# Master.net
KiCad netlist of a schematic drawn in Altium Designer
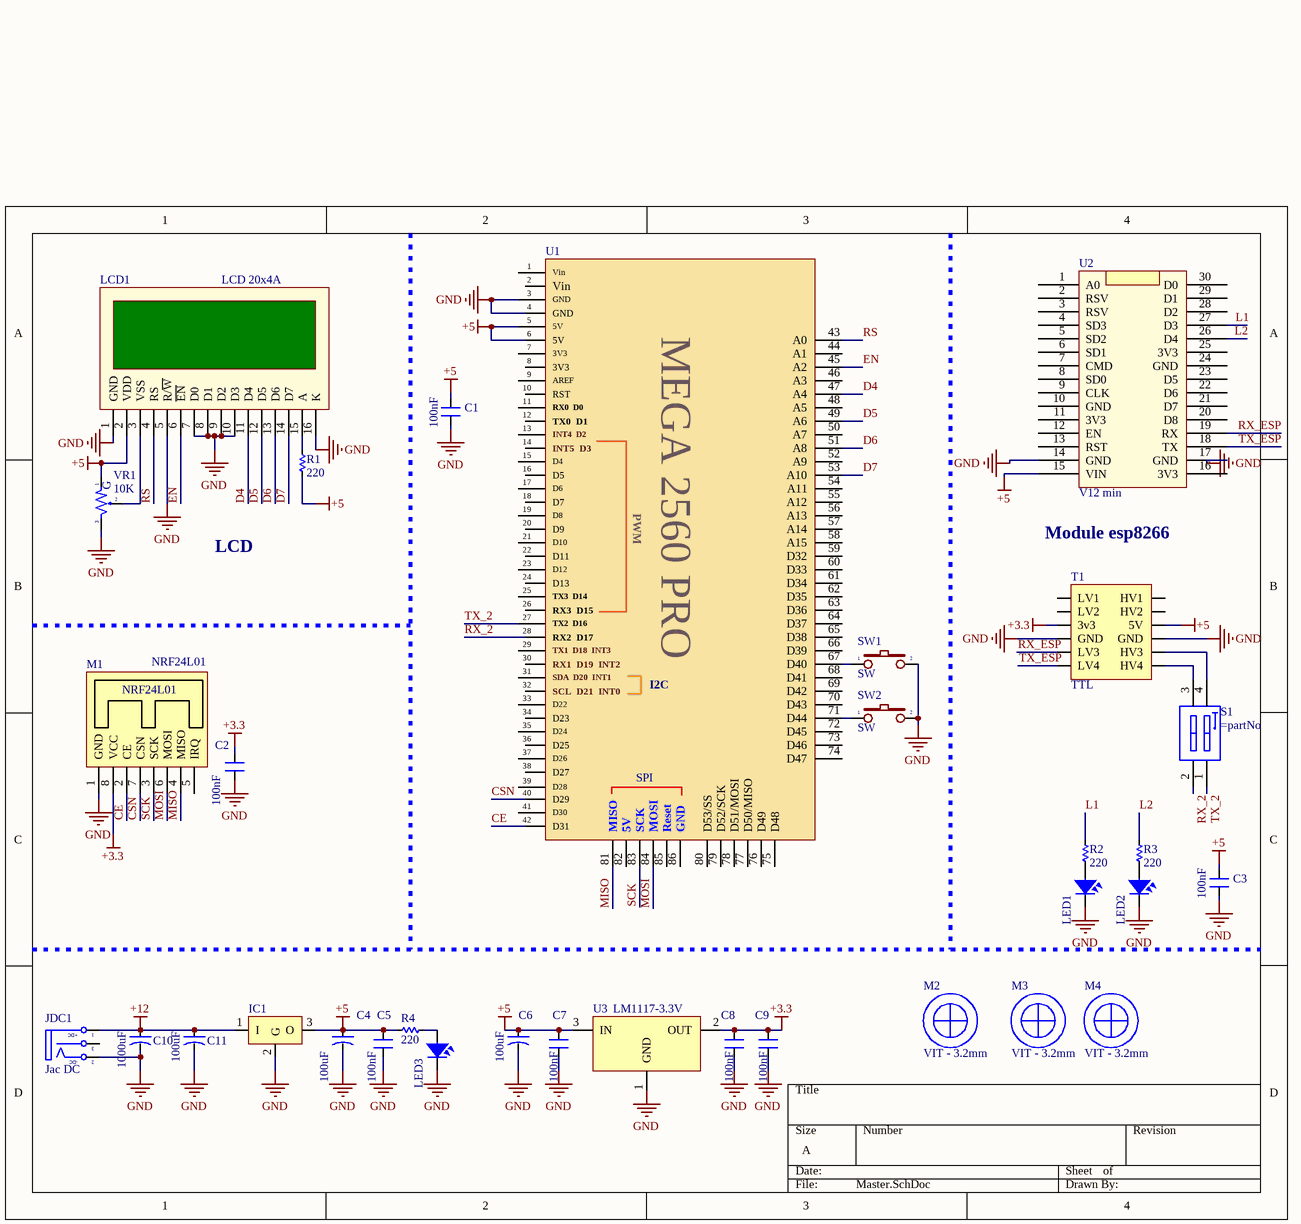
[diagram p0: Master.SchDoc]

(export (version "E")
  (design (tool "Eeschema 10.0.6"))
  (components
    (comp (ref "C1") (value "100nF") (footprint "CN1.5") (libsource (lib "thu vien 3d") (part "CN")))
    (comp (ref "C2") (value "100nF") (footprint "CN1.5") (libsource (lib "thu vien 3d") (part "CN")))
    (comp (ref "C3") (value "100nF") (footprint "CN1.5") (libsource (lib "thu vien 3d") (part "CN")))
    (comp (ref "C4")
      (value "100uF")
      (footprint "CA-ALU-5")
      (description "Capacitor (Semiconductor SIM Model)")
      (fields (field (name "PUBLISHER") "Altium Limited"))
      (libsource (lib "thu vien 3d") (part "CN-ALU-DIP"))
    )
    (comp (ref "C5") (value "100nF") (footprint "CN1.5") (libsource (lib "thu vien 3d") (part "CN")))
    (comp (ref "C6")
      (value "100uF")
      (footprint "CA-ALU-5")
      (description "Capacitor (Semiconductor SIM Model)")
      (fields (field (name "PUBLISHER") "Altium Limited"))
      (libsource (lib "thu vien 3d") (part "CN-ALU-DIP"))
    )
    (comp (ref "C7") (value "100nF") (footprint "CN1.5") (libsource (lib "thu vien 3d") (part "CN")))
    (comp (ref "C8") (value "100nF") (footprint "CN1.5") (libsource (lib "thu vien 3d") (part "CN")))
    (comp (ref "C9") (value "100nF") (footprint "CN1.5") (libsource (lib "thu vien 3d") (part "CN")))
    (comp (ref "C10")
      (value "1000uF")
      (footprint "CA-ALU-6.3")
      (description "Capacitor (Semiconductor SIM Model)")
      (fields (field (name "PUBLISHER") "Altium Limited"))
      (libsource (lib "thu vien 3d") (part "CN-ALU-DIP"))
    )
    (comp (ref "C11")
      (value "100uF")
      (footprint "CA-ALU-5")
      (description "Capacitor (Semiconductor SIM Model)")
      (fields (field (name "PUBLISHER") "Altium Limited"))
      (libsource (lib "thu vien 3d") (part "CN-ALU-DIP"))
    )
    (comp (ref "IC1")
      (value "LM78xx")
      (footprint "TO220-123")
      (description "Positive Voltage Regulator")
      (fields (field (name "PUBLISHER") "Altium Limited"))
      (libsource (lib "thu vien 3d") (part "LM78xx"))
    )
    (comp (ref "JDC1")
      (value "Jac DC")
      (footprint "DC0")
      (description "Jac DC input")
      (libsource (lib "thu vien 3d") (part "DCIN"))
    )
    (comp (ref "LCD1")
      (value "LCD 20x4A")
      (footprint "LCD20X4A")
      (description "LCD dipslay 20 char, 4 line")
      (libsource (lib "thu vien 3d") (part "LCD20x4A"))
    )
    (comp (ref "LED1")
      (value "LED")
      (footprint "LED-3MM-RED")
      (description "LED Single colour Green and Red")
      (libsource (lib "thu vien 3d") (part "LED"))
    )
    (comp (ref "LED2")
      (value "LED")
      (footprint "LED-3MM-RED")
      (description "LED Single colour Green and Red")
      (libsource (lib "thu vien 3d") (part "LED"))
    )
    (comp (ref "LED3")
      (value "LED")
      (footprint "LED-3MM-RED")
      (description "LED Single colour Green and Red")
      (libsource (lib "thu vien 3d") (part "LED"))
    )
    (comp (ref "M1")
      (value "NRF24L01")
      (footprint "NRF24L01")
      (libsource (lib "thu vien 3d") (part "NRF24L01"))
    )
    (comp (ref "M2")
      (value "VIT - 3.2mm")
      (footprint "VIT - 3.2MM_2")
      (libsource (lib "Nichietsuvn") (part "VIT - 3.2mm"))
    )
    (comp (ref "M3")
      (value "VIT - 3.2mm")
      (footprint "VIT - 3.2MM_2")
      (libsource (lib "Nichietsuvn") (part "VIT - 3.2mm"))
    )
    (comp (ref "M4")
      (value "VIT - 3.2mm")
      (footprint "VIT - 3.2MM_2")
      (libsource (lib "Nichietsuvn") (part "VIT - 3.2mm"))
    )
    (comp (ref "R1")
      (value "220")
      (footprint "RES-1/4W-SMALL")
      (description "Res")
      (fields
        (field (name "MANUFACTURER") "Generic Components")
        (field (name "PUBLISHER") "Altium Hobart Technology Centre")
      )
      (libsource (lib "thu vien 3d") (part "Res"))
    )
    (comp (ref "R2")
      (value "220")
      (footprint "RES-1/4WD")
      (description "Res")
      (fields
        (field (name "MANUFACTURER") "Generic Components")
        (field (name "PUBLISHER") "Altium Hobart Technology Centre")
      )
      (libsource (lib "thu vien 3d") (part "Res"))
    )
    (comp (ref "R3")
      (value "220")
      (footprint "RES-1/4WD")
      (description "Res")
      (fields
        (field (name "MANUFACTURER") "Generic Components")
        (field (name "PUBLISHER") "Altium Hobart Technology Centre")
      )
      (libsource (lib "thu vien 3d") (part "Res"))
    )
    (comp (ref "R4")
      (value "220")
      (footprint "RES-1/4W")
      (description "Res")
      (fields
        (field (name "MANUFACTURER") "Generic Components")
        (field (name "PUBLISHER") "Altium Hobart Technology Centre")
      )
      (libsource (lib "thu vien 3d") (part "Res"))
    )
    (comp (ref "S1")
      (value "~")
      (footprint "SW-DIP2")
      (description "WS-DITV 2.54 mm small compact THT flat actuator with top tape")
      (fields
        (field (name "MANUFACTURER") "Wurth Elektronik")
        (field (name "PART NO.") "418127160902")
        (field (name "CREATED BY") "Baojun Chen")
      )
      (libsource (lib "thu vien 3d") (part "SWDIP2"))
    )
    (comp (ref "SW1")
      (value "SW")
      (footprint "SW1-DIP")
      (description "Switch button 2 pin")
      (libsource (lib "thu vien 3d") (part "SW2"))
    )
    (comp (ref "SW2")
      (value "SW")
      (footprint "SW1-DIP")
      (description "Switch button 2 pin")
      (libsource (lib "thu vien 3d") (part "SW2"))
    )
    (comp (ref "T1")
      (value "TTL")
      (footprint "TTL")
      (description "WR-PHD 2.54 mm Dual Socket Header")
      (fields
        (field (name "MANUFACTURER") "Würth Elektronik eiSos GmbH")
        (field (name "PARTNO") "61301221821")
        (field (name "CREATED BY") "Karrer Zheng")
      )
      (libsource (lib "Nichietsuvn") (part "TTL"))
    )
    (comp (ref "U1")
      (value "Le Quoc Huy")
      (footprint "Arduino Mega Pro Mini")
      (libsource (lib "LIB_HUY_isolator") (part "Arduino mega 2560 Pro"))
    )
    (comp (ref "U2")
      (value "V12 min")
      (footprint "Module ESP 8266_min")
      (libsource (lib "Nichietsuvn") (part "Module ESP8266"))
    )
    (comp (ref "U3")
      (value "LM1117-3.3V")
      (footprint "SOT223")
      (description "800mA Low-Dropout Linear Regulator")
      (fields (field (name "CREATOR") "Nguyen Ba Bien"))
      (libsource (lib "thu vien 3d") (part "LM1117"))
    )
    (comp (ref "VR1")
      (value "10K")
      (footprint "VR-S3")
      (description "Var Resistor")
      (libsource (lib "thu vien 3d") (part "VR-S"))
    )
  )
  (nets
    (net (code "1") (name "+3.3") (class "Default")
      (node (ref "C2") (pin "2") (pinfunction "2_2") (pintype "passive"))
      (node (ref "C8") (pin "2") (pinfunction "2_2") (pintype "passive"))
      (node (ref "C9") (pin "2") (pinfunction "2_2") (pintype "passive"))
      (node (ref "M1") (pin "8") (pinfunction "VCC_8") (pintype "passive"))
      (node (ref "T1") (pin "3") (pinfunction "3v3_3") (pintype "passive"))
      (node (ref "U3") (pin "2") (pinfunction "OUT_2") (pintype "passive"))
    )
    (net (code "2") (name "+5") (class "Default")
      (node (ref "C1") (pin "2") (pinfunction "2_2") (pintype "passive"))
      (node (ref "C3") (pin "2") (pinfunction "2_2") (pintype "passive"))
      (node (ref "C4") (pin "1") (pinfunction "1_1") (pintype "passive"))
      (node (ref "C5") (pin "2") (pinfunction "2_2") (pintype "passive"))
      (node (ref "C6") (pin "1") (pinfunction "1_1") (pintype "passive"))
      (node (ref "C7") (pin "2") (pinfunction "2_2") (pintype "passive"))
      (node (ref "IC1") (pin "3") (pinfunction "O_3") (pintype "power_in"))
      (node (ref "LCD1") (pin "2") (pinfunction "VDD_2") (pintype "passive"))
      (node (ref "R1") (pin "2") (pinfunction "2_2") (pintype "passive"))
      (node (ref "R4") (pin "2") (pinfunction "2_2") (pintype "passive"))
      (node (ref "T1") (pin "10") (pinfunction "5V_10") (pintype "passive"))
      (node (ref "U1") (pin "5") (pinfunction "5V_5") (pintype "passive"))
      (node (ref "U1") (pin "6") (pinfunction "5V_6") (pintype "passive"))
      (node (ref "U2") (pin "15") (pinfunction "VIN_15") (pintype "passive"))
      (node (ref "U3") (pin "3") (pinfunction "IN_3") (pintype "passive"))
      (node (ref "VR1") (pin "1") (pinfunction "1_1") (pintype "passive"))
    )
    (net (code "3") (name "+12") (class "Default")
      (node (ref "C10") (pin "1") (pinfunction "1_1") (pintype "passive"))
      (node (ref "C11") (pin "1") (pinfunction "1_1") (pintype "passive"))
      (node (ref "IC1") (pin "1") (pinfunction "I_1") (pintype "power_in"))
      (node (ref "JDC1") (pin "1") (pinfunction "T_1") (pintype "passive"))
    )
    (net (code "4") (name "/CE") (class "Default")
      (node (ref "M1") (pin "2") (pinfunction "CE_2") (pintype "passive"))
      (node (ref "U1") (pin "42") (pinfunction "D31_42") (pintype "passive"))
    )
    (net (code "5") (name "/CSN") (class "Default")
      (node (ref "M1") (pin "7") (pinfunction "CSN_7") (pintype "passive"))
      (node (ref "U1") (pin "40") (pinfunction "D29_40") (pintype "passive"))
    )
    (net (code "6") (name "/D4") (class "Default")
      (node (ref "LCD1") (pin "11") (pinfunction "D4_11") (pintype "passive"))
      (node (ref "U1") (pin "47") (pinfunction "A4_47") (pintype "passive"))
    )
    (net (code "7") (name "/D5") (class "Default")
      (node (ref "LCD1") (pin "12") (pinfunction "D5_12") (pintype "passive"))
      (node (ref "U1") (pin "49") (pinfunction "A6_49") (pintype "passive"))
    )
    (net (code "8") (name "/D6") (class "Default")
      (node (ref "LCD1") (pin "13") (pinfunction "D6_13") (pintype "passive"))
      (node (ref "U1") (pin "51") (pinfunction "A8_51") (pintype "passive"))
    )
    (net (code "9") (name "/D7") (class "Default")
      (node (ref "LCD1") (pin "14") (pinfunction "D7_14") (pintype "passive"))
      (node (ref "U1") (pin "53") (pinfunction "A10_53") (pintype "passive"))
    )
    (net (code "10") (name "/EN") (class "Default")
      (node (ref "LCD1") (pin "6") (pinfunction "~{EN}_6") (pintype "passive"))
      (node (ref "U1") (pin "45") (pinfunction "A2_45") (pintype "passive"))
    )
    (net (code "11") (name "/L1") (class "Default")
      (node (ref "R2") (pin "2") (pinfunction "2_2") (pintype "passive"))
      (node (ref "U2") (pin "27") (pinfunction "D3_27") (pintype "passive"))
    )
    (net (code "12") (name "/L2") (class "Default")
      (node (ref "R3") (pin "2") (pinfunction "2_2") (pintype "passive"))
      (node (ref "U2") (pin "26") (pinfunction "D4_26") (pintype "passive"))
    )
    (net (code "13") (name "/MISO") (class "Default")
      (node (ref "M1") (pin "4") (pinfunction "MISO_4") (pintype "passive"))
      (node (ref "U1") (pin "81") (pinfunction "MISO_81") (pintype "passive"))
    )
    (net (code "14") (name "/MOSI") (class "Default")
      (node (ref "M1") (pin "6") (pinfunction "MOSI_6") (pintype "passive"))
      (node (ref "U1") (pin "84") (pinfunction "MOSI_84") (pintype "passive"))
    )
    (net (code "15") (name "/RS") (class "Default")
      (node (ref "LCD1") (pin "4") (pinfunction "RS_4") (pintype "passive"))
      (node (ref "U1") (pin "43") (pinfunction "A0_43") (pintype "passive"))
    )
    (net (code "16") (name "/RX_2") (class "Default")
      (node (ref "S1") (pin "2") (pinfunction "2_2") (pintype "passive"))
      (node (ref "U1") (pin "28") (pinfunction "RX2__D17_28") (pintype "passive"))
    )
    (net (code "17") (name "/RX_ESP") (class "Default")
      (node (ref "T1") (pin "5") (pinfunction "LV3_5") (pintype "passive"))
      (node (ref "U2") (pin "19") (pinfunction "RX_19") (pintype "passive"))
    )
    (net (code "18") (name "/SCK") (class "Default")
      (node (ref "M1") (pin "3") (pinfunction "SCK_3") (pintype "passive"))
      (node (ref "U1") (pin "83") (pinfunction "SCK_83") (pintype "passive"))
    )
    (net (code "19") (name "/TX_2") (class "Default")
      (node (ref "S1") (pin "1") (pinfunction "1_1") (pintype "passive"))
      (node (ref "U1") (pin "27") (pinfunction "TX2__D16_27") (pintype "passive"))
    )
    (net (code "20") (name "/TX_ESP") (class "Default")
      (node (ref "T1") (pin "6") (pinfunction "LV4_6") (pintype "passive"))
      (node (ref "U2") (pin "18") (pinfunction "TX_18") (pintype "passive"))
    )
    (net (code "21") (name "GND") (class "Default")
      (node (ref "C1") (pin "1") (pinfunction "1_1") (pintype "passive"))
      (node (ref "C10") (pin "2") (pinfunction "2_2") (pintype "passive"))
      (node (ref "C11") (pin "2") (pinfunction "2_2") (pintype "passive"))
      (node (ref "C2") (pin "1") (pinfunction "1_1") (pintype "passive"))
      (node (ref "C3") (pin "1") (pinfunction "1_1") (pintype "passive"))
      (node (ref "C4") (pin "2") (pinfunction "2_2") (pintype "passive"))
      (node (ref "C5") (pin "1") (pinfunction "1_1") (pintype "passive"))
      (node (ref "C6") (pin "2") (pinfunction "2_2") (pintype "passive"))
      (node (ref "C7") (pin "1") (pinfunction "1_1") (pintype "passive"))
      (node (ref "C8") (pin "1") (pinfunction "1_1") (pintype "passive"))
      (node (ref "C9") (pin "1") (pinfunction "1_1") (pintype "passive"))
      (node (ref "IC1") (pin "2") (pinfunction "G_2") (pintype "power_in"))
      (node (ref "JDC1") (pin "2") (pinfunction "TN_2") (pintype "passive"))
      (node (ref "LCD1") (pin "1") (pinfunction "GND_1") (pintype "passive"))
      (node (ref "LCD1") (pin "10") (pinfunction "D3_10") (pintype "passive"))
      (node (ref "LCD1") (pin "16") (pinfunction "K_16") (pintype "passive"))
      (node (ref "LCD1") (pin "5") (pinfunction "R/~{W}_5") (pintype "passive"))
      (node (ref "LCD1") (pin "7") (pinfunction "D0_7") (pintype "passive"))
      (node (ref "LCD1") (pin "8") (pinfunction "D1_8") (pintype "passive"))
      (node (ref "LCD1") (pin "9") (pinfunction "D2_9") (pintype "passive"))
      (node (ref "LED1") (pin "2") (pinfunction "2_2") (pintype "passive"))
      (node (ref "LED2") (pin "2") (pinfunction "2_2") (pintype "passive"))
      (node (ref "LED3") (pin "2") (pinfunction "2_2") (pintype "passive"))
      (node (ref "M1") (pin "1") (pinfunction "GND_1") (pintype "passive"))
      (node (ref "SW1") (pin "2") (pinfunction "2_2") (pintype "passive"))
      (node (ref "SW2") (pin "2") (pinfunction "2_2") (pintype "passive"))
      (node (ref "T1") (pin "4") (pinfunction "GND_4") (pintype "passive"))
      (node (ref "T1") (pin "9") (pinfunction "GND_9") (pintype "passive"))
      (node (ref "U1") (pin "3") (pinfunction "GND_3") (pintype "passive"))
      (node (ref "U1") (pin "4") (pinfunction "GND_4") (pintype "passive"))
      (node (ref "U2") (pin "14") (pinfunction "GND_14") (pintype "passive"))
      (node (ref "U2") (pin "17") (pinfunction "GND_17") (pintype "passive"))
      (node (ref "U3") (pin "1") (pinfunction "GND_1") (pintype "passive"))
      (node (ref "VR1") (pin "3") (pinfunction "3_3") (pintype "passive"))
    )
    (net (code "22") (name "Net-(LCD1-A)") (class "Default")
      (node (ref "LCD1") (pin "15") (pinfunction "A_15") (pintype "passive"))
      (node (ref "R1") (pin "1") (pinfunction "1_1") (pintype "passive"))
    )
    (net (code "23") (name "Net-(LCD1-VSS)") (class "Default")
      (node (ref "LCD1") (pin "3") (pinfunction "VSS_3") (pintype "passive"))
      (node (ref "VR1") (pin "2") (pinfunction "2_2") (pintype "passive"))
    )
    (net (code "24") (name "Net-(LED1-Pad1)") (class "Default")
      (node (ref "LED1") (pin "1") (pinfunction "1_1") (pintype "passive"))
      (node (ref "R2") (pin "1") (pinfunction "1_1") (pintype "passive"))
    )
    (net (code "25") (name "Net-(LED2-Pad1)") (class "Default")
      (node (ref "LED2") (pin "1") (pinfunction "1_1") (pintype "passive"))
      (node (ref "R3") (pin "1") (pinfunction "1_1") (pintype "passive"))
    )
    (net (code "26") (name "Net-(LED3-Pad1)") (class "Default")
      (node (ref "LED3") (pin "1") (pinfunction "1_1") (pintype "passive"))
      (node (ref "R4") (pin "1") (pinfunction "1_1") (pintype "passive"))
    )
    (net (code "27") (name "Net-(T1-HV3)") (class "Default")
      (node (ref "S1") (pin "4") (pinfunction "4_4") (pintype "passive"))
      (node (ref "T1") (pin "8") (pinfunction "HV3_8") (pintype "passive"))
    )
    (net (code "28") (name "Net-(T1-HV4)") (class "Default")
      (node (ref "S1") (pin "3") (pinfunction "3_3") (pintype "passive"))
      (node (ref "T1") (pin "7") (pinfunction "HV4_7") (pintype "passive"))
    )
    (net (code "29") (name "Net-(U1-D40)") (class "Default")
      (node (ref "SW1") (pin "1") (pinfunction "1_1") (pintype "passive"))
      (node (ref "U1") (pin "67") (pinfunction "D40_67") (pintype "passive"))
    )
    (net (code "30") (name "Net-(U1-D44)") (class "Default")
      (node (ref "SW2") (pin "1") (pinfunction "1_1") (pintype "passive"))
      (node (ref "U1") (pin "71") (pinfunction "D44_71") (pintype "passive"))
    )
    (net (code "31") (name "unconnected-(JDC1-S-Pad3)") (class "Default")
      (node (ref "JDC1") (pin "3") (pinfunction "S_3") (pintype "power_in"))
    )
    (net (code "32") (name "unconnected-(M1-IRQ-Pad5)") (class "Default")
      (node (ref "M1") (pin "5") (pinfunction "IRQ_5") (pintype "passive"))
    )
    (net (code "33") (name "unconnected-(T1-HV1-Pad12)") (class "Default")
      (node (ref "T1") (pin "12") (pinfunction "HV1_12") (pintype "passive"))
    )
    (net (code "34") (name "unconnected-(T1-HV2-Pad11)") (class "Default")
      (node (ref "T1") (pin "11") (pinfunction "HV2_11") (pintype "passive"))
    )
    (net (code "35") (name "unconnected-(T1-LV1-Pad1)") (class "Default")
      (node (ref "T1") (pin "1") (pinfunction "LV1_1") (pintype "passive"))
    )
    (net (code "36") (name "unconnected-(T1-LV2-Pad2)") (class "Default")
      (node (ref "T1") (pin "2") (pinfunction "LV2_2") (pintype "passive"))
    )
    (net (code "37") (name "unconnected-(U1-3V3-Pad7)") (class "Default")
      (node (ref "U1") (pin "7") (pinfunction "3V3_7") (pintype "passive"))
    )
    (net (code "38") (name "unconnected-(U1-3V3-Pad8)") (class "Default")
      (node (ref "U1") (pin "8") (pinfunction "3V3_8") (pintype "passive"))
    )
    (net (code "39") (name "unconnected-(U1-5V-Pad82)") (class "Default")
      (node (ref "U1") (pin "82") (pinfunction "5V_82") (pintype "passive"))
    )
    (net (code "40") (name "unconnected-(U1-A1-Pad44)") (class "Default")
      (node (ref "U1") (pin "44") (pinfunction "A1_44") (pintype "passive"))
    )
    (net (code "41") (name "unconnected-(U1-A3-Pad46)") (class "Default")
      (node (ref "U1") (pin "46") (pinfunction "A3_46") (pintype "passive"))
    )
    (net (code "42") (name "unconnected-(U1-A5-Pad48)") (class "Default")
      (node (ref "U1") (pin "48") (pinfunction "A5_48") (pintype "passive"))
    )
    (net (code "43") (name "unconnected-(U1-A7-Pad50)") (class "Default")
      (node (ref "U1") (pin "50") (pinfunction "A7_50") (pintype "passive"))
    )
    (net (code "44") (name "unconnected-(U1-A9-Pad52)") (class "Default")
      (node (ref "U1") (pin "52") (pinfunction "A9_52") (pintype "passive"))
    )
    (net (code "45") (name "unconnected-(U1-A11-Pad54)") (class "Default")
      (node (ref "U1") (pin "54") (pinfunction "A11_54") (pintype "passive"))
    )
    (net (code "46") (name "unconnected-(U1-A12-Pad55)") (class "Default")
      (node (ref "U1") (pin "55") (pinfunction "A12_55") (pintype "passive"))
    )
    (net (code "47") (name "unconnected-(U1-A13-Pad56)") (class "Default")
      (node (ref "U1") (pin "56") (pinfunction "A13_56") (pintype "passive"))
    )
    (net (code "48") (name "unconnected-(U1-A14-Pad57)") (class "Default")
      (node (ref "U1") (pin "57") (pinfunction "A14_57") (pintype "passive"))
    )
    (net (code "49") (name "unconnected-(U1-A15-Pad58)") (class "Default")
      (node (ref "U1") (pin "58") (pinfunction "A15_58") (pintype "passive"))
    )
    (net (code "50") (name "unconnected-(U1-AREF-Pad9)") (class "Default")
      (node (ref "U1") (pin "9") (pinfunction "AREF_9") (pintype "passive"))
    )
    (net (code "51") (name "unconnected-(U1-D4-Pad15)") (class "Default")
      (node (ref "U1") (pin "15") (pinfunction "D4_15") (pintype "passive"))
    )
    (net (code "52") (name "unconnected-(U1-D5-Pad16)") (class "Default")
      (node (ref "U1") (pin "16") (pinfunction "D5_16") (pintype "passive"))
    )
    (net (code "53") (name "unconnected-(U1-D6-Pad17)") (class "Default")
      (node (ref "U1") (pin "17") (pinfunction "D6_17") (pintype "passive"))
    )
    (net (code "54") (name "unconnected-(U1-D7-Pad18)") (class "Default")
      (node (ref "U1") (pin "18") (pinfunction "D7_18") (pintype "passive"))
    )
    (net (code "55") (name "unconnected-(U1-D8-Pad19)") (class "Default")
      (node (ref "U1") (pin "19") (pinfunction "D8_19") (pintype "passive"))
    )
    (net (code "56") (name "unconnected-(U1-D9-Pad20)") (class "Default")
      (node (ref "U1") (pin "20") (pinfunction "D9_20") (pintype "passive"))
    )
    (net (code "57") (name "unconnected-(U1-D10-Pad21)") (class "Default")
      (node (ref "U1") (pin "21") (pinfunction "D10_21") (pintype "passive"))
    )
    (net (code "58") (name "unconnected-(U1-D11-Pad22)") (class "Default")
      (node (ref "U1") (pin "22") (pinfunction "D11_22") (pintype "passive"))
    )
    (net (code "59") (name "unconnected-(U1-D12-Pad23)") (class "Default")
      (node (ref "U1") (pin "23") (pinfunction "D12_23") (pintype "passive"))
    )
    (net (code "60") (name "unconnected-(U1-D13-Pad24)") (class "Default")
      (node (ref "U1") (pin "24") (pinfunction "D13_24") (pintype "passive"))
    )
    (net (code "61") (name "unconnected-(U1-D22-Pad33)") (class "Default")
      (node (ref "U1") (pin "33") (pinfunction "D22_33") (pintype "passive"))
    )
    (net (code "62") (name "unconnected-(U1-D23-Pad34)") (class "Default")
      (node (ref "U1") (pin "34") (pinfunction "D23_34") (pintype "passive"))
    )
    (net (code "63") (name "unconnected-(U1-D24-Pad35)") (class "Default")
      (node (ref "U1") (pin "35") (pinfunction "D24_35") (pintype "passive"))
    )
    (net (code "64") (name "unconnected-(U1-D25-Pad36)") (class "Default")
      (node (ref "U1") (pin "36") (pinfunction "D25_36") (pintype "passive"))
    )
    (net (code "65") (name "unconnected-(U1-D26-Pad37)") (class "Default")
      (node (ref "U1") (pin "37") (pinfunction "D26_37") (pintype "passive"))
    )
    (net (code "66") (name "unconnected-(U1-D27-Pad38)") (class "Default")
      (node (ref "U1") (pin "38") (pinfunction "D27_38") (pintype "passive"))
    )
    (net (code "67") (name "unconnected-(U1-D28-Pad39)") (class "Default")
      (node (ref "U1") (pin "39") (pinfunction "D28_39") (pintype "passive"))
    )
    (net (code "68") (name "unconnected-(U1-D30-Pad41)") (class "Default")
      (node (ref "U1") (pin "41") (pinfunction "D30_41") (pintype "passive"))
    )
    (net (code "69") (name "unconnected-(U1-D32-Pad59)") (class "Default")
      (node (ref "U1") (pin "59") (pinfunction "D32_59") (pintype "passive"))
    )
    (net (code "70") (name "unconnected-(U1-D33-Pad60)") (class "Default")
      (node (ref "U1") (pin "60") (pinfunction "D33_60") (pintype "passive"))
    )
    (net (code "71") (name "unconnected-(U1-D34-Pad61)") (class "Default")
      (node (ref "U1") (pin "61") (pinfunction "D34_61") (pintype "passive"))
    )
    (net (code "72") (name "unconnected-(U1-D35-Pad62)") (class "Default")
      (node (ref "U1") (pin "62") (pinfunction "D35_62") (pintype "passive"))
    )
    (net (code "73") (name "unconnected-(U1-D36-Pad63)") (class "Default")
      (node (ref "U1") (pin "63") (pinfunction "D36_63") (pintype "passive"))
    )
    (net (code "74") (name "unconnected-(U1-D37-Pad64)") (class "Default")
      (node (ref "U1") (pin "64") (pinfunction "D37_64") (pintype "passive"))
    )
    (net (code "75") (name "unconnected-(U1-D38-Pad65)") (class "Default")
      (node (ref "U1") (pin "65") (pinfunction "D38_65") (pintype "passive"))
    )
    (net (code "76") (name "unconnected-(U1-D39-Pad66)") (class "Default")
      (node (ref "U1") (pin "66") (pinfunction "D39_66") (pintype "passive"))
    )
    (net (code "77") (name "unconnected-(U1-D41-Pad68)") (class "Default")
      (node (ref "U1") (pin "68") (pinfunction "D41_68") (pintype "passive"))
    )
    (net (code "78") (name "unconnected-(U1-D42-Pad69)") (class "Default")
      (node (ref "U1") (pin "69") (pinfunction "D42_69") (pintype "passive"))
    )
    (net (code "79") (name "unconnected-(U1-D43-Pad70)") (class "Default")
      (node (ref "U1") (pin "70") (pinfunction "D43_70") (pintype "passive"))
    )
    (net (code "80") (name "unconnected-(U1-D45-Pad72)") (class "Default")
      (node (ref "U1") (pin "72") (pinfunction "D45_72") (pintype "passive"))
    )
    (net (code "81") (name "unconnected-(U1-D46-Pad73)") (class "Default")
      (node (ref "U1") (pin "73") (pinfunction "D46_73") (pintype "passive"))
    )
    (net (code "82") (name "unconnected-(U1-D47-Pad74)") (class "Default")
      (node (ref "U1") (pin "74") (pinfunction "D47_74") (pintype "passive"))
    )
    (net (code "83") (name "unconnected-(U1-D48-Pad75)") (class "Default")
      (node (ref "U1") (pin "75") (pinfunction "D48_75") (pintype "passive"))
    )
    (net (code "84") (name "unconnected-(U1-D49-Pad76)") (class "Default")
      (node (ref "U1") (pin "76") (pinfunction "D49_76") (pintype "passive"))
    )
    (net (code "85") (name "unconnected-(U1-D50{slash}MISO-Pad77)") (class "Default")
      (node (ref "U1") (pin "77") (pinfunction "D50/MISO_77") (pintype "passive"))
    )
    (net (code "86") (name "unconnected-(U1-D51{slash}MOSI-Pad78)") (class "Default")
      (node (ref "U1") (pin "78") (pinfunction "D51/MOSI_78") (pintype "passive"))
    )
    (net (code "87") (name "unconnected-(U1-D52{slash}SCK-Pad79)") (class "Default")
      (node (ref "U1") (pin "79") (pinfunction "D52/SCK_79") (pintype "passive"))
    )
    (net (code "88") (name "unconnected-(U1-D53{slash}SS-Pad80)") (class "Default")
      (node (ref "U1") (pin "80") (pinfunction "D53/SS_80") (pintype "passive"))
    )
    (net (code "89") (name "unconnected-(U1-GND-Pad86)") (class "Default")
      (node (ref "U1") (pin "86") (pinfunction "GND_86") (pintype "passive"))
    )
    (net (code "90") (name "unconnected-(U1-INT4__D2-Pad13)") (class "Default")
      (node (ref "U1") (pin "13") (pinfunction "INT4__D2_13") (pintype "passive"))
    )
    (net (code "91") (name "unconnected-(U1-INT5__D3-Pad14)") (class "Default")
      (node (ref "U1") (pin "14") (pinfunction "INT5__D3_14") (pintype "passive"))
    )
    (net (code "92") (name "unconnected-(U1-RST-Pad10)") (class "Default")
      (node (ref "U1") (pin "10") (pinfunction "RST_10") (pintype "passive"))
    )
    (net (code "93") (name "unconnected-(U1-RX0__D0-Pad11)") (class "Default")
      (node (ref "U1") (pin "11") (pinfunction "RX0__D0_11") (pintype "passive"))
    )
    (net (code "94") (name "unconnected-(U1-RX1__D19__INT2-Pad30)") (class "Default")
      (node (ref "U1") (pin "30") (pinfunction "RX1__D19__INT2_30") (pintype "passive"))
    )
    (net (code "95") (name "unconnected-(U1-RX3__D15-Pad26)") (class "Default")
      (node (ref "U1") (pin "26") (pinfunction "RX3__D15_26") (pintype "passive"))
    )
    (net (code "96") (name "unconnected-(U1-Reset-Pad85)") (class "Default")
      (node (ref "U1") (pin "85") (pinfunction "Reset_85") (pintype "passive"))
    )
    (net (code "97") (name "unconnected-(U1-SCL__D21__INT0-Pad32)") (class "Default")
      (node (ref "U1") (pin "32") (pinfunction "SCL__D21__INT0_32") (pintype "passive"))
    )
    (net (code "98") (name "unconnected-(U1-SDA__D20__INT1-Pad31)") (class "Default")
      (node (ref "U1") (pin "31") (pinfunction "SDA__D20__INT1_31") (pintype "passive"))
    )
    (net (code "99") (name "unconnected-(U1-TX0__D1-Pad12)") (class "Default")
      (node (ref "U1") (pin "12") (pinfunction "TX0__D1_12") (pintype "passive"))
    )
    (net (code "100") (name "unconnected-(U1-TX1__D18__INT3-Pad29)") (class "Default")
      (node (ref "U1") (pin "29") (pinfunction "TX1__D18__INT3_29") (pintype "passive"))
    )
    (net (code "101") (name "unconnected-(U1-TX3__D14-Pad25)") (class "Default")
      (node (ref "U1") (pin "25") (pinfunction "TX3__D14_25") (pintype "passive"))
    )
    (net (code "102") (name "unconnected-(U1-Vin-Pad1)") (class "Default")
      (node (ref "U1") (pin "1") (pinfunction "Vin_1") (pintype "passive"))
    )
    (net (code "103") (name "unconnected-(U1-Vin-Pad2)") (class "Default")
      (node (ref "U1") (pin "2") (pinfunction "Vin_2") (pintype "passive"))
    )
    (net (code "104") (name "unconnected-(U2-3V3-Pad11)") (class "Default")
      (node (ref "U2") (pin "11") (pinfunction "3V3_11") (pintype "passive"))
    )
    (net (code "105") (name "unconnected-(U2-3V3-Pad16)") (class "Default")
      (node (ref "U2") (pin "16") (pinfunction "3V3_16") (pintype "passive"))
    )
    (net (code "106") (name "unconnected-(U2-3V3-Pad25)") (class "Default")
      (node (ref "U2") (pin "25") (pinfunction "3V3_25") (pintype "passive"))
    )
    (net (code "107") (name "unconnected-(U2-A0-Pad1)") (class "Default")
      (node (ref "U2") (pin "1") (pinfunction "A0_1") (pintype "passive"))
    )
    (net (code "108") (name "unconnected-(U2-CLK-Pad9)") (class "Default")
      (node (ref "U2") (pin "9") (pinfunction "CLK_9") (pintype "passive"))
    )
    (net (code "109") (name "unconnected-(U2-CMD-Pad7)") (class "Default")
      (node (ref "U2") (pin "7") (pinfunction "CMD_7") (pintype "passive"))
    )
    (net (code "110") (name "unconnected-(U2-D0-Pad30)") (class "Default")
      (node (ref "U2") (pin "30") (pinfunction "D0_30") (pintype "passive"))
    )
    (net (code "111") (name "unconnected-(U2-D1-Pad29)") (class "Default")
      (node (ref "U2") (pin "29") (pinfunction "D1_29") (pintype "passive"))
    )
    (net (code "112") (name "unconnected-(U2-D2-Pad28)") (class "Default")
      (node (ref "U2") (pin "28") (pinfunction "D2_28") (pintype "passive"))
    )
    (net (code "113") (name "unconnected-(U2-D5-Pad23)") (class "Default")
      (node (ref "U2") (pin "23") (pinfunction "D5_23") (pintype "passive"))
    )
    (net (code "114") (name "unconnected-(U2-D6-Pad22)") (class "Default")
      (node (ref "U2") (pin "22") (pinfunction "D6_22") (pintype "passive"))
    )
    (net (code "115") (name "unconnected-(U2-D7-Pad21)") (class "Default")
      (node (ref "U2") (pin "21") (pinfunction "D7_21") (pintype "passive"))
    )
    (net (code "116") (name "unconnected-(U2-D8-Pad20)") (class "Default")
      (node (ref "U2") (pin "20") (pinfunction "D8_20") (pintype "passive"))
    )
    (net (code "117") (name "unconnected-(U2-EN-Pad12)") (class "Default")
      (node (ref "U2") (pin "12") (pinfunction "EN_12") (pintype "passive"))
    )
    (net (code "118") (name "unconnected-(U2-GND-Pad10)") (class "Default")
      (node (ref "U2") (pin "10") (pinfunction "GND_10") (pintype "passive"))
    )
    (net (code "119") (name "unconnected-(U2-GND-Pad24)") (class "Default")
      (node (ref "U2") (pin "24") (pinfunction "GND_24") (pintype "passive"))
    )
    (net (code "120") (name "unconnected-(U2-RST-Pad13)") (class "Default")
      (node (ref "U2") (pin "13") (pinfunction "RST_13") (pintype "passive"))
    )
    (net (code "121") (name "unconnected-(U2-RSV-Pad2)") (class "Default")
      (node (ref "U2") (pin "2") (pinfunction "RSV_2") (pintype "passive"))
    )
    (net (code "122") (name "unconnected-(U2-RSV-Pad3)") (class "Default")
      (node (ref "U2") (pin "3") (pinfunction "RSV_3") (pintype "passive"))
    )
    (net (code "123") (name "unconnected-(U2-SD0-Pad8)") (class "Default")
      (node (ref "U2") (pin "8") (pinfunction "SD0_8") (pintype "passive"))
    )
    (net (code "124") (name "unconnected-(U2-SD1-Pad6)") (class "Default")
      (node (ref "U2") (pin "6") (pinfunction "SD1_6") (pintype "passive"))
    )
    (net (code "125") (name "unconnected-(U2-SD2-Pad5)") (class "Default")
      (node (ref "U2") (pin "5") (pinfunction "SD2_5") (pintype "passive"))
    )
    (net (code "126") (name "unconnected-(U2-SD3-Pad4)") (class "Default")
      (node (ref "U2") (pin "4") (pinfunction "SD3_4") (pintype "passive"))
    )
  )
)
